# RFSWITCH_v2.net
KiCad netlist of a schematic drawn in EAGLE
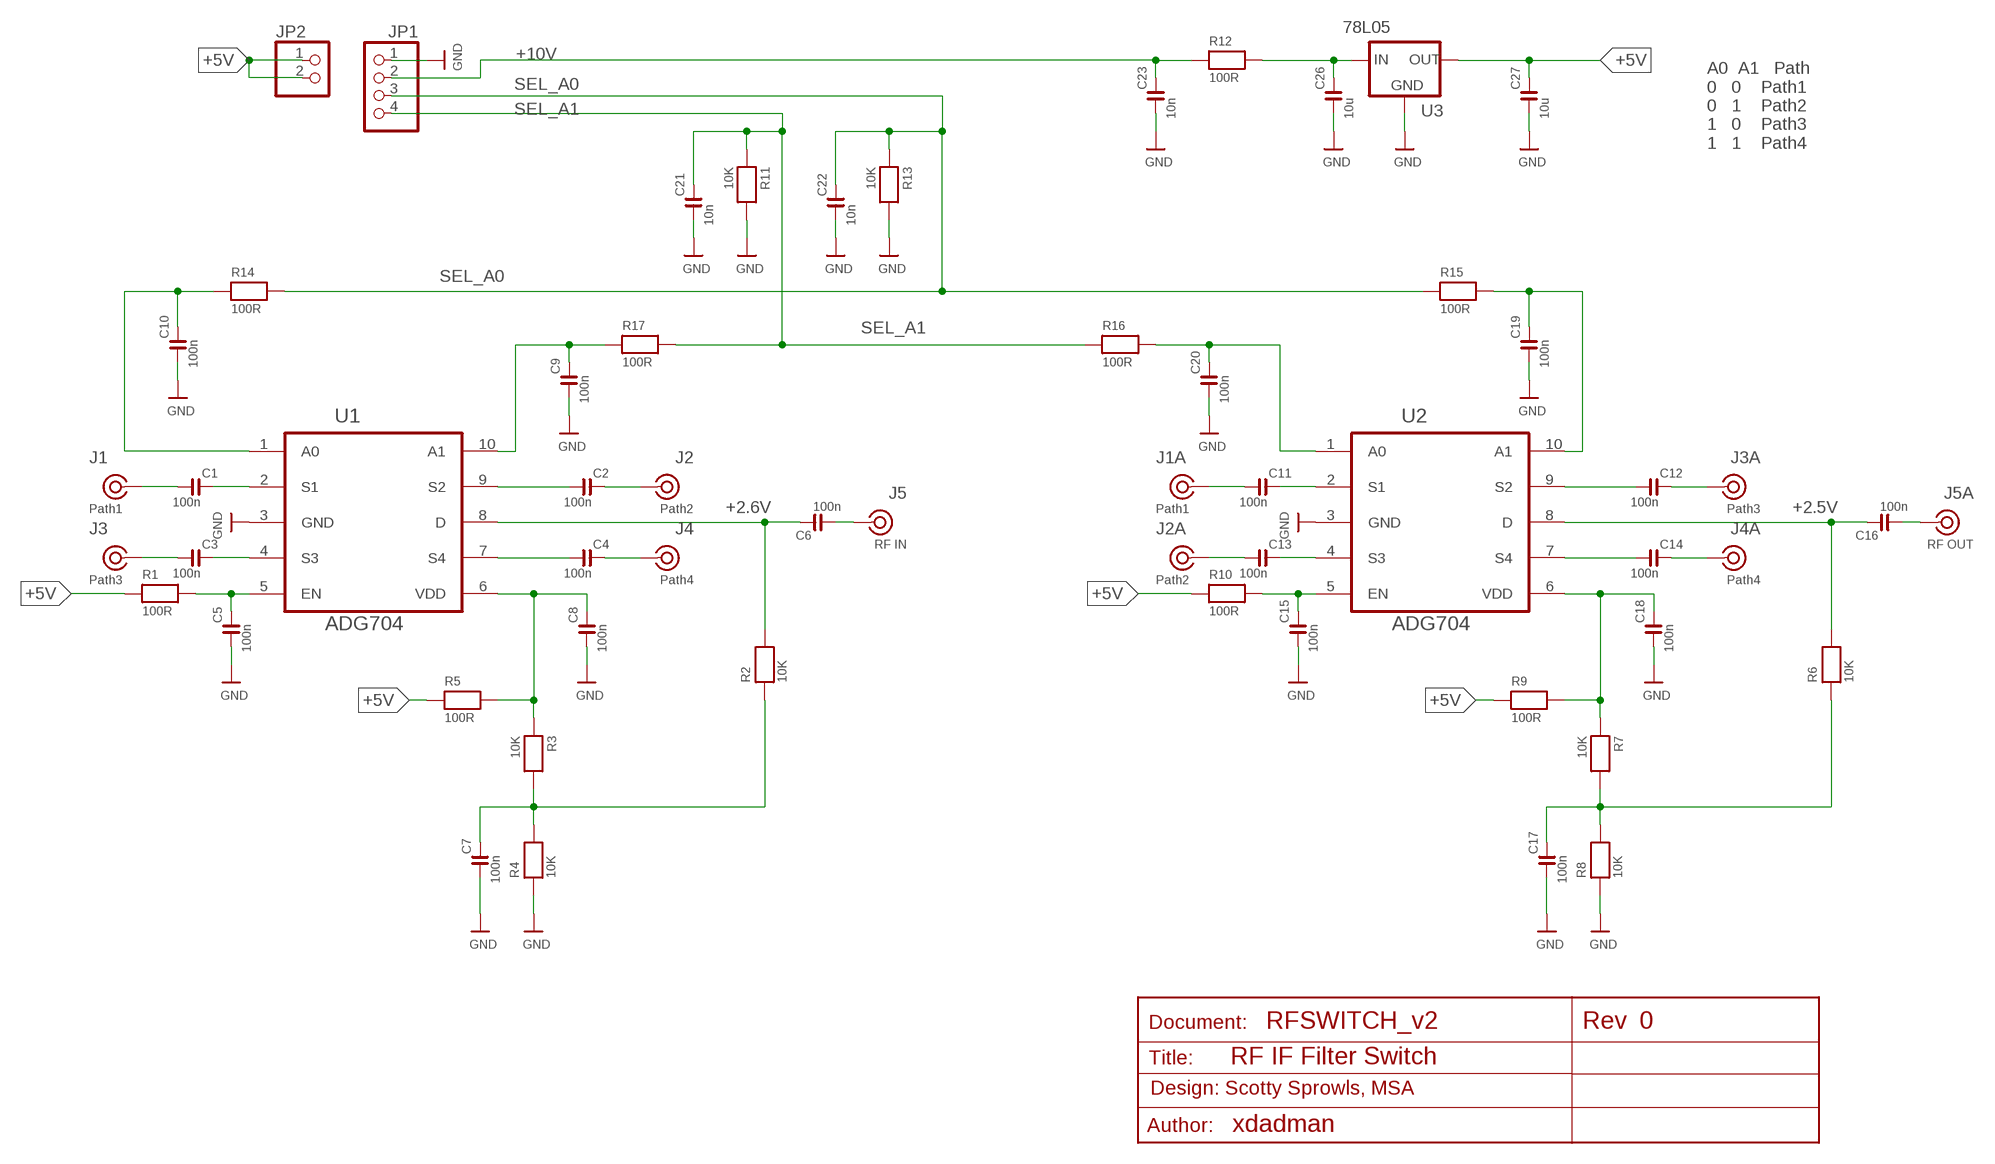
[diagram p0: schematic, sheet 1]

(export (version "E")
  (design (tool "Eeschema 10.0.6"))
  (components
    (comp (ref "C1")
      (value "100n")
      (footprint "eagle-import:C0805")
      (libsource (lib "eagle-import") (part "C0805100N"))
    )
    (comp (ref "C2")
      (value "100n")
      (footprint "eagle-import:C0805")
      (libsource (lib "eagle-import") (part "C0805100N"))
    )
    (comp (ref "C3")
      (value "100n")
      (footprint "eagle-import:C0805")
      (libsource (lib "eagle-import") (part "C0805100N"))
    )
    (comp (ref "C4")
      (value "100n")
      (footprint "eagle-import:C0805")
      (libsource (lib "eagle-import") (part "C0805100N"))
    )
    (comp (ref "C5")
      (value "100n")
      (footprint "eagle-import:C0603")
      (libsource (lib "eagle-import") (part "CC0603100NF"))
    )
    (comp (ref "C6")
      (value "100n")
      (footprint "eagle-import:C0805")
      (libsource (lib "eagle-import") (part "C0805100N"))
    )
    (comp (ref "C7")
      (value "100n")
      (footprint "eagle-import:C0805")
      (libsource (lib "eagle-import") (part "C0805100N"))
    )
    (comp (ref "C8")
      (value "100n")
      (footprint "eagle-import:C0603")
      (libsource (lib "eagle-import") (part "CC0603100NF"))
    )
    (comp (ref "C9")
      (value "100n")
      (footprint "eagle-import:C0805")
      (libsource (lib "eagle-import") (part "C0805100N"))
    )
    (comp (ref "C10")
      (value "100n")
      (footprint "eagle-import:C0805")
      (libsource (lib "eagle-import") (part "C0805100N"))
    )
    (comp (ref "C11")
      (value "100n")
      (footprint "eagle-import:C0805")
      (libsource (lib "eagle-import") (part "C0805100N"))
    )
    (comp (ref "C12")
      (value "100n")
      (footprint "eagle-import:C0805")
      (libsource (lib "eagle-import") (part "C0805100N"))
    )
    (comp (ref "C13")
      (value "100n")
      (footprint "eagle-import:C0805")
      (libsource (lib "eagle-import") (part "C0805100N"))
    )
    (comp (ref "C14")
      (value "100n")
      (footprint "eagle-import:C0805")
      (libsource (lib "eagle-import") (part "C0805100N"))
    )
    (comp (ref "C15")
      (value "100n")
      (footprint "eagle-import:C0603")
      (libsource (lib "eagle-import") (part "CC0603100NF"))
    )
    (comp (ref "C16")
      (value "100n")
      (footprint "eagle-import:C0805")
      (libsource (lib "eagle-import") (part "C0805100N"))
    )
    (comp (ref "C17")
      (value "100n")
      (footprint "eagle-import:C0805")
      (libsource (lib "eagle-import") (part "C0805100N"))
    )
    (comp (ref "C18")
      (value "100n")
      (footprint "eagle-import:C0603")
      (libsource (lib "eagle-import") (part "CC0603100NF"))
    )
    (comp (ref "C19")
      (value "100n")
      (footprint "eagle-import:C0805")
      (libsource (lib "eagle-import") (part "C0805100N"))
    )
    (comp (ref "C20")
      (value "100n")
      (footprint "eagle-import:C0805")
      (libsource (lib "eagle-import") (part "C0805100N"))
    )
    (comp (ref "C21")
      (value "10n")
      (footprint "eagle-import:C0805")
      (libsource (lib "eagle-import") (part "C080510N"))
    )
    (comp (ref "C22")
      (value "10n")
      (footprint "eagle-import:C0805")
      (libsource (lib "eagle-import") (part "C080510N"))
    )
    (comp (ref "C23")
      (value "10n")
      (footprint "eagle-import:C0805")
      (libsource (lib "eagle-import") (part "C080510N"))
    )
    (comp (ref "C26")
      (value "10u")
      (footprint "eagle-import:C1206")
      (libsource (lib "eagle-import") (part "CC120610U"))
    )
    (comp (ref "C27")
      (value "10u")
      (footprint "eagle-import:C1206")
      (libsource (lib "eagle-import") (part "CC120610U"))
    )
    (comp (ref "J1")
      (value "Path1")
      (footprint "eagle-import:SLIM_COAX_PAD")
      (libsource (lib "eagle-import") (part "COAX"))
    )
    (comp (ref "J1A")
      (value "Path1")
      (footprint "eagle-import:SLIM_COAX_PAD")
      (libsource (lib "eagle-import") (part "COAX"))
    )
    (comp (ref "J2")
      (value "Path2")
      (footprint "eagle-import:SLIM_COAX_PAD")
      (libsource (lib "eagle-import") (part "COAX"))
    )
    (comp (ref "J2A")
      (value "Path2")
      (footprint "eagle-import:SLIM_COAX_PAD")
      (libsource (lib "eagle-import") (part "COAX"))
    )
    (comp (ref "J3")
      (value "Path3")
      (footprint "eagle-import:SLIM_COAX_PAD")
      (libsource (lib "eagle-import") (part "COAX"))
    )
    (comp (ref "J3A")
      (value "Path3")
      (footprint "eagle-import:SLIM_COAX_PAD")
      (libsource (lib "eagle-import") (part "COAX"))
    )
    (comp (ref "J4")
      (value "Path4")
      (footprint "eagle-import:SLIM_COAX_PAD")
      (libsource (lib "eagle-import") (part "COAX"))
    )
    (comp (ref "J4A")
      (value "Path4")
      (footprint "eagle-import:SLIM_COAX_PAD")
      (libsource (lib "eagle-import") (part "COAX"))
    )
    (comp (ref "J5")
      (value "RF IN")
      (footprint "eagle-import:SLIM_COAX_PAD")
      (libsource (lib "eagle-import") (part "COAX"))
    )
    (comp (ref "J5A")
      (value "RF OUT")
      (footprint "eagle-import:SLIM_COAX_PAD")
      (libsource (lib "eagle-import") (part "COAX"))
    )
    (comp (ref "JP1")
      (value "PINHD-1X4")
      (footprint "eagle-import:1X04")
      (libsource (lib "eagle-import") (part "PINHD-1X4"))
    )
    (comp (ref "JP2")
      (value "PINHD-1X2")
      (footprint "eagle-import:1X02")
      (libsource (lib "eagle-import") (part "PINHD-1X2"))
    )
    (comp (ref "R1")
      (value "100R")
      (footprint "eagle-import:C0805")
      (libsource (lib "eagle-import") (part "R0805100R"))
    )
    (comp (ref "R2")
      (value "10K")
      (footprint "eagle-import:R0805")
      (libsource (lib "eagle-import") (part "R080510K"))
    )
    (comp (ref "R3")
      (value "10K")
      (footprint "eagle-import:R0805")
      (libsource (lib "eagle-import") (part "R080510K"))
    )
    (comp (ref "R4")
      (value "10K")
      (footprint "eagle-import:R0805")
      (libsource (lib "eagle-import") (part "R080510K"))
    )
    (comp (ref "R5")
      (value "100R")
      (footprint "eagle-import:C0805")
      (libsource (lib "eagle-import") (part "R0805100R"))
    )
    (comp (ref "R6")
      (value "10K")
      (footprint "eagle-import:R0805")
      (libsource (lib "eagle-import") (part "R080510K"))
    )
    (comp (ref "R7")
      (value "10K")
      (footprint "eagle-import:R0805")
      (libsource (lib "eagle-import") (part "R080510K"))
    )
    (comp (ref "R8")
      (value "10K")
      (footprint "eagle-import:R0805")
      (libsource (lib "eagle-import") (part "R080510K"))
    )
    (comp (ref "R9")
      (value "100R")
      (footprint "eagle-import:C0805")
      (libsource (lib "eagle-import") (part "R0805100R"))
    )
    (comp (ref "R10")
      (value "100R")
      (footprint "eagle-import:C0805")
      (libsource (lib "eagle-import") (part "R0805100R"))
    )
    (comp (ref "R11")
      (value "10K")
      (footprint "eagle-import:R0805")
      (libsource (lib "eagle-import") (part "R080510K"))
    )
    (comp (ref "R12")
      (value "100R")
      (footprint "eagle-import:C0805")
      (libsource (lib "eagle-import") (part "R0805100R"))
    )
    (comp (ref "R13")
      (value "10K")
      (footprint "eagle-import:R0805")
      (libsource (lib "eagle-import") (part "R080510K"))
    )
    (comp (ref "R14")
      (value "100R")
      (footprint "eagle-import:C0805")
      (libsource (lib "eagle-import") (part "R0805100R"))
    )
    (comp (ref "R15")
      (value "100R")
      (footprint "eagle-import:C0805")
      (libsource (lib "eagle-import") (part "R0805100R"))
    )
    (comp (ref "R16")
      (value "100R")
      (footprint "eagle-import:C0805")
      (libsource (lib "eagle-import") (part "R0805100R"))
    )
    (comp (ref "R17")
      (value "100R")
      (footprint "eagle-import:C0805")
      (libsource (lib "eagle-import") (part "R0805100R"))
    )
    (comp (ref "U1")
      (value "ADG704")
      (footprint "eagle-import:SOP50P490X110-10N-ADG704")
      (fields (field (name "MPN") "ADG704BRMZ"))
      (libsource (lib "eagle-import") (part "ADG704BRMZ"))
    )
    (comp (ref "U2")
      (value "ADG704")
      (footprint "eagle-import:SOP50P490X110-10N-ADG704")
      (fields (field (name "MPN") "ADG704BRMZ"))
      (libsource (lib "eagle-import") (part "ADG704BRMZ"))
    )
    (comp (ref "U3")
      (value "78L05")
      (footprint "eagle-import:SOT89")
      (libsource (lib "eagle-import") (part "78MXXL78L05"))
    )
  )
  (nets
    (net (code "1") (name "+5V") (class "Default")
      (node (ref "C27") (pin "2") (pinfunction "2_2") (pintype "passive"))
      (node (ref "JP2") (pin "1") (pinfunction "1_1") (pintype "passive"))
      (node (ref "JP2") (pin "2") (pinfunction "2_2") (pintype "passive"))
      (node (ref "R1") (pin "1") (pinfunction "1_1") (pintype "passive"))
      (node (ref "R10") (pin "1") (pinfunction "1_1") (pintype "passive"))
      (node (ref "R5") (pin "1") (pinfunction "1_1") (pintype "passive"))
      (node (ref "R9") (pin "1") (pinfunction "1_1") (pintype "passive"))
      (node (ref "U3") (pin "1") (pinfunction "OUT_1") (pintype "passive"))
    )
    (net (code "2") (name "/+10V") (class "Default")
      (node (ref "C23") (pin "2") (pinfunction "2_2") (pintype "passive"))
      (node (ref "JP1") (pin "2") (pinfunction "2_2") (pintype "passive"))
      (node (ref "R12") (pin "1") (pinfunction "1_1") (pintype "passive"))
    )
    (net (code "3") (name "/SEL_A0") (class "Default")
      (node (ref "C22") (pin "2") (pinfunction "2_2") (pintype "passive"))
      (node (ref "JP1") (pin "3") (pinfunction "3_3") (pintype "passive"))
      (node (ref "R13") (pin "1") (pinfunction "1_1") (pintype "passive"))
      (node (ref "R14") (pin "2") (pinfunction "2_2") (pintype "passive"))
      (node (ref "R15") (pin "1") (pinfunction "1_1") (pintype "passive"))
    )
    (net (code "4") (name "/SEL_A1") (class "Default")
      (node (ref "C21") (pin "2") (pinfunction "2_2") (pintype "passive"))
      (node (ref "JP1") (pin "4") (pinfunction "4_4") (pintype "passive"))
      (node (ref "R11") (pin "1") (pinfunction "1_1") (pintype "passive"))
      (node (ref "R16") (pin "1") (pinfunction "1_1") (pintype "passive"))
      (node (ref "R17") (pin "2") (pinfunction "2_2") (pintype "passive"))
    )
    (net (code "5") (name "GND") (class "Default")
      (node (ref "C10") (pin "1") (pinfunction "1_1") (pintype "passive"))
      (node (ref "C15") (pin "1") (pinfunction "1_1") (pintype "passive"))
      (node (ref "C17") (pin "1") (pinfunction "1_1") (pintype "passive"))
      (node (ref "C18") (pin "1") (pinfunction "1_1") (pintype "passive"))
      (node (ref "C19") (pin "1") (pinfunction "1_1") (pintype "passive"))
      (node (ref "C20") (pin "1") (pinfunction "1_1") (pintype "passive"))
      (node (ref "C21") (pin "1") (pinfunction "1_1") (pintype "passive"))
      (node (ref "C22") (pin "1") (pinfunction "1_1") (pintype "passive"))
      (node (ref "C23") (pin "1") (pinfunction "1_1") (pintype "passive"))
      (node (ref "C26") (pin "1") (pinfunction "1_1") (pintype "passive"))
      (node (ref "C27") (pin "1") (pinfunction "1_1") (pintype "passive"))
      (node (ref "C5") (pin "1") (pinfunction "1_1") (pintype "passive"))
      (node (ref "C7") (pin "1") (pinfunction "1_1") (pintype "passive"))
      (node (ref "C8") (pin "1") (pinfunction "1_1") (pintype "passive"))
      (node (ref "C9") (pin "1") (pinfunction "1_1") (pintype "passive"))
      (node (ref "JP1") (pin "1") (pinfunction "1_1") (pintype "passive"))
      (node (ref "R11") (pin "2") (pinfunction "2_2") (pintype "passive"))
      (node (ref "R13") (pin "2") (pinfunction "2_2") (pintype "passive"))
      (node (ref "R4") (pin "1") (pinfunction "1_1") (pintype "passive"))
      (node (ref "R8") (pin "1") (pinfunction "1_1") (pintype "passive"))
      (node (ref "U1") (pin "3") (pinfunction "GND_3") (pintype "passive"))
      (node (ref "U2") (pin "3") (pinfunction "GND_3") (pintype "passive"))
      (node (ref "U3") (pin "2") (pinfunction "GND_2") (pintype "input"))
      (node (ref "U3") (pin "4") (pinfunction "GND_4") (pintype "input"))
    )
    (net (code "6") (name "Net-(C7-Pad2)") (class "Default")
      (node (ref "C7") (pin "2") (pinfunction "2_2") (pintype "passive"))
      (node (ref "R2") (pin "1") (pinfunction "1_1") (pintype "passive"))
      (node (ref "R3") (pin "2") (pinfunction "2_2") (pintype "passive"))
      (node (ref "R4") (pin "2") (pinfunction "2_2") (pintype "passive"))
    )
    (net (code "7") (name "Net-(C17-Pad2)") (class "Default")
      (node (ref "C17") (pin "2") (pinfunction "2_2") (pintype "passive"))
      (node (ref "R6") (pin "1") (pinfunction "1_1") (pintype "passive"))
      (node (ref "R7") (pin "2") (pinfunction "2_2") (pintype "passive"))
      (node (ref "R8") (pin "2") (pinfunction "2_2") (pintype "passive"))
    )
    (net (code "8") (name "Net-(J1A-1)") (class "Default")
      (node (ref "C1") (pin "1") (pinfunction "1_1") (pintype "passive"))
      (node (ref "J1") (pin "SIG") (pinfunction "1_SIG") (pintype "passive"))
    )
    (net (code "9") (name "Net-(J1AA-1)") (class "Default")
      (node (ref "C11") (pin "1") (pinfunction "1_1") (pintype "passive"))
      (node (ref "J1A") (pin "SIG") (pinfunction "1_SIG") (pintype "passive"))
    )
    (net (code "10") (name "Net-(J2A-1)") (class "Default")
      (node (ref "C2") (pin "2") (pinfunction "2_2") (pintype "passive"))
      (node (ref "J2") (pin "SIG") (pinfunction "1_SIG") (pintype "passive"))
    )
    (net (code "11") (name "Net-(J2AA-1)") (class "Default")
      (node (ref "C13") (pin "1") (pinfunction "1_1") (pintype "passive"))
      (node (ref "J2A") (pin "SIG") (pinfunction "1_SIG") (pintype "passive"))
    )
    (net (code "12") (name "Net-(J3A-1)") (class "Default")
      (node (ref "C3") (pin "1") (pinfunction "1_1") (pintype "passive"))
      (node (ref "J3") (pin "SIG") (pinfunction "1_SIG") (pintype "passive"))
    )
    (net (code "13") (name "Net-(J3AA-1)") (class "Default")
      (node (ref "C12") (pin "2") (pinfunction "2_2") (pintype "passive"))
      (node (ref "J3A") (pin "SIG") (pinfunction "1_SIG") (pintype "passive"))
    )
    (net (code "14") (name "Net-(J4A-1)") (class "Default")
      (node (ref "C4") (pin "2") (pinfunction "2_2") (pintype "passive"))
      (node (ref "J4") (pin "SIG") (pinfunction "1_SIG") (pintype "passive"))
    )
    (net (code "15") (name "Net-(J4AA-1)") (class "Default")
      (node (ref "C14") (pin "2") (pinfunction "2_2") (pintype "passive"))
      (node (ref "J4A") (pin "SIG") (pinfunction "1_SIG") (pintype "passive"))
    )
    (net (code "16") (name "Net-(J5A-1)") (class "Default")
      (node (ref "C6") (pin "1") (pinfunction "1_1") (pintype "passive"))
      (node (ref "J5") (pin "SIG") (pinfunction "1_SIG") (pintype "passive"))
    )
    (net (code "17") (name "Net-(J5AA-1)") (class "Default")
      (node (ref "C16") (pin "1") (pinfunction "1_1") (pintype "passive"))
      (node (ref "J5A") (pin "SIG") (pinfunction "1_SIG") (pintype "passive"))
    )
    (net (code "18") (name "Net-(U1-A0)") (class "Default")
      (node (ref "C10") (pin "2") (pinfunction "2_2") (pintype "passive"))
      (node (ref "R14") (pin "1") (pinfunction "1_1") (pintype "passive"))
      (node (ref "U1") (pin "1") (pinfunction "A0_1") (pintype "input"))
    )
    (net (code "19") (name "Net-(U1-A1)") (class "Default")
      (node (ref "C9") (pin "2") (pinfunction "2_2") (pintype "passive"))
      (node (ref "R17") (pin "1") (pinfunction "1_1") (pintype "passive"))
      (node (ref "U1") (pin "10") (pinfunction "A1_10") (pintype "input"))
    )
    (net (code "20") (name "Net-(U1-D)") (class "Default")
      (node (ref "C6") (pin "2") (pinfunction "2_2") (pintype "passive"))
      (node (ref "R2") (pin "2") (pinfunction "2_2") (pintype "passive"))
      (node (ref "U1") (pin "8") (pinfunction "D_8") (pintype "bidirectional"))
    )
    (net (code "21") (name "Net-(U1-EN)") (class "Default")
      (node (ref "C5") (pin "2") (pinfunction "2_2") (pintype "passive"))
      (node (ref "R1") (pin "2") (pinfunction "2_2") (pintype "passive"))
      (node (ref "U1") (pin "5") (pinfunction "EN_5") (pintype "input"))
    )
    (net (code "22") (name "Net-(U1-S1)") (class "Default")
      (node (ref "C1") (pin "2") (pinfunction "2_2") (pintype "passive"))
      (node (ref "U1") (pin "2") (pinfunction "S1_2") (pintype "bidirectional"))
    )
    (net (code "23") (name "Net-(U1-S2)") (class "Default")
      (node (ref "C2") (pin "1") (pinfunction "1_1") (pintype "passive"))
      (node (ref "U1") (pin "9") (pinfunction "S2_9") (pintype "bidirectional"))
    )
    (net (code "24") (name "Net-(U1-S3)") (class "Default")
      (node (ref "C3") (pin "2") (pinfunction "2_2") (pintype "passive"))
      (node (ref "U1") (pin "4") (pinfunction "S3_4") (pintype "bidirectional"))
    )
    (net (code "25") (name "Net-(U1-S4)") (class "Default")
      (node (ref "C4") (pin "1") (pinfunction "1_1") (pintype "passive"))
      (node (ref "U1") (pin "7") (pinfunction "S4_7") (pintype "bidirectional"))
    )
    (net (code "26") (name "Net-(U1-VDD)") (class "Default")
      (node (ref "C8") (pin "2") (pinfunction "2_2") (pintype "passive"))
      (node (ref "R3") (pin "1") (pinfunction "1_1") (pintype "passive"))
      (node (ref "R5") (pin "2") (pinfunction "2_2") (pintype "passive"))
      (node (ref "U1") (pin "6") (pinfunction "VDD_6") (pintype "power_in"))
    )
    (net (code "27") (name "Net-(U2-A0)") (class "Default")
      (node (ref "C20") (pin "2") (pinfunction "2_2") (pintype "passive"))
      (node (ref "R16") (pin "2") (pinfunction "2_2") (pintype "passive"))
      (node (ref "U2") (pin "1") (pinfunction "A0_1") (pintype "input"))
    )
    (net (code "28") (name "Net-(U2-A1)") (class "Default")
      (node (ref "C19") (pin "2") (pinfunction "2_2") (pintype "passive"))
      (node (ref "R15") (pin "2") (pinfunction "2_2") (pintype "passive"))
      (node (ref "U2") (pin "10") (pinfunction "A1_10") (pintype "input"))
    )
    (net (code "29") (name "Net-(U2-D)") (class "Default")
      (node (ref "C16") (pin "2") (pinfunction "2_2") (pintype "passive"))
      (node (ref "R6") (pin "2") (pinfunction "2_2") (pintype "passive"))
      (node (ref "U2") (pin "8") (pinfunction "D_8") (pintype "bidirectional"))
    )
    (net (code "30") (name "Net-(U2-EN)") (class "Default")
      (node (ref "C15") (pin "2") (pinfunction "2_2") (pintype "passive"))
      (node (ref "R10") (pin "2") (pinfunction "2_2") (pintype "passive"))
      (node (ref "U2") (pin "5") (pinfunction "EN_5") (pintype "input"))
    )
    (net (code "31") (name "Net-(U2-S1)") (class "Default")
      (node (ref "C11") (pin "2") (pinfunction "2_2") (pintype "passive"))
      (node (ref "U2") (pin "2") (pinfunction "S1_2") (pintype "bidirectional"))
    )
    (net (code "32") (name "Net-(U2-S2)") (class "Default")
      (node (ref "C12") (pin "1") (pinfunction "1_1") (pintype "passive"))
      (node (ref "U2") (pin "9") (pinfunction "S2_9") (pintype "bidirectional"))
    )
    (net (code "33") (name "Net-(U2-S3)") (class "Default")
      (node (ref "C13") (pin "2") (pinfunction "2_2") (pintype "passive"))
      (node (ref "U2") (pin "4") (pinfunction "S3_4") (pintype "bidirectional"))
    )
    (net (code "34") (name "Net-(U2-S4)") (class "Default")
      (node (ref "C14") (pin "1") (pinfunction "1_1") (pintype "passive"))
      (node (ref "U2") (pin "7") (pinfunction "S4_7") (pintype "bidirectional"))
    )
    (net (code "35") (name "Net-(U2-VDD)") (class "Default")
      (node (ref "C18") (pin "2") (pinfunction "2_2") (pintype "passive"))
      (node (ref "R7") (pin "1") (pinfunction "1_1") (pintype "passive"))
      (node (ref "R9") (pin "2") (pinfunction "2_2") (pintype "passive"))
      (node (ref "U2") (pin "6") (pinfunction "VDD_6") (pintype "power_in"))
    )
    (net (code "36") (name "Net-(U3-IN)") (class "Default")
      (node (ref "C26") (pin "2") (pinfunction "2_2") (pintype "passive"))
      (node (ref "R12") (pin "2") (pinfunction "2_2") (pintype "passive"))
      (node (ref "U3") (pin "3") (pinfunction "IN_3") (pintype "input"))
    )
  )
)
